# Power_Supply.net
KiCad netlist of a schematic drawn in Altium Designer
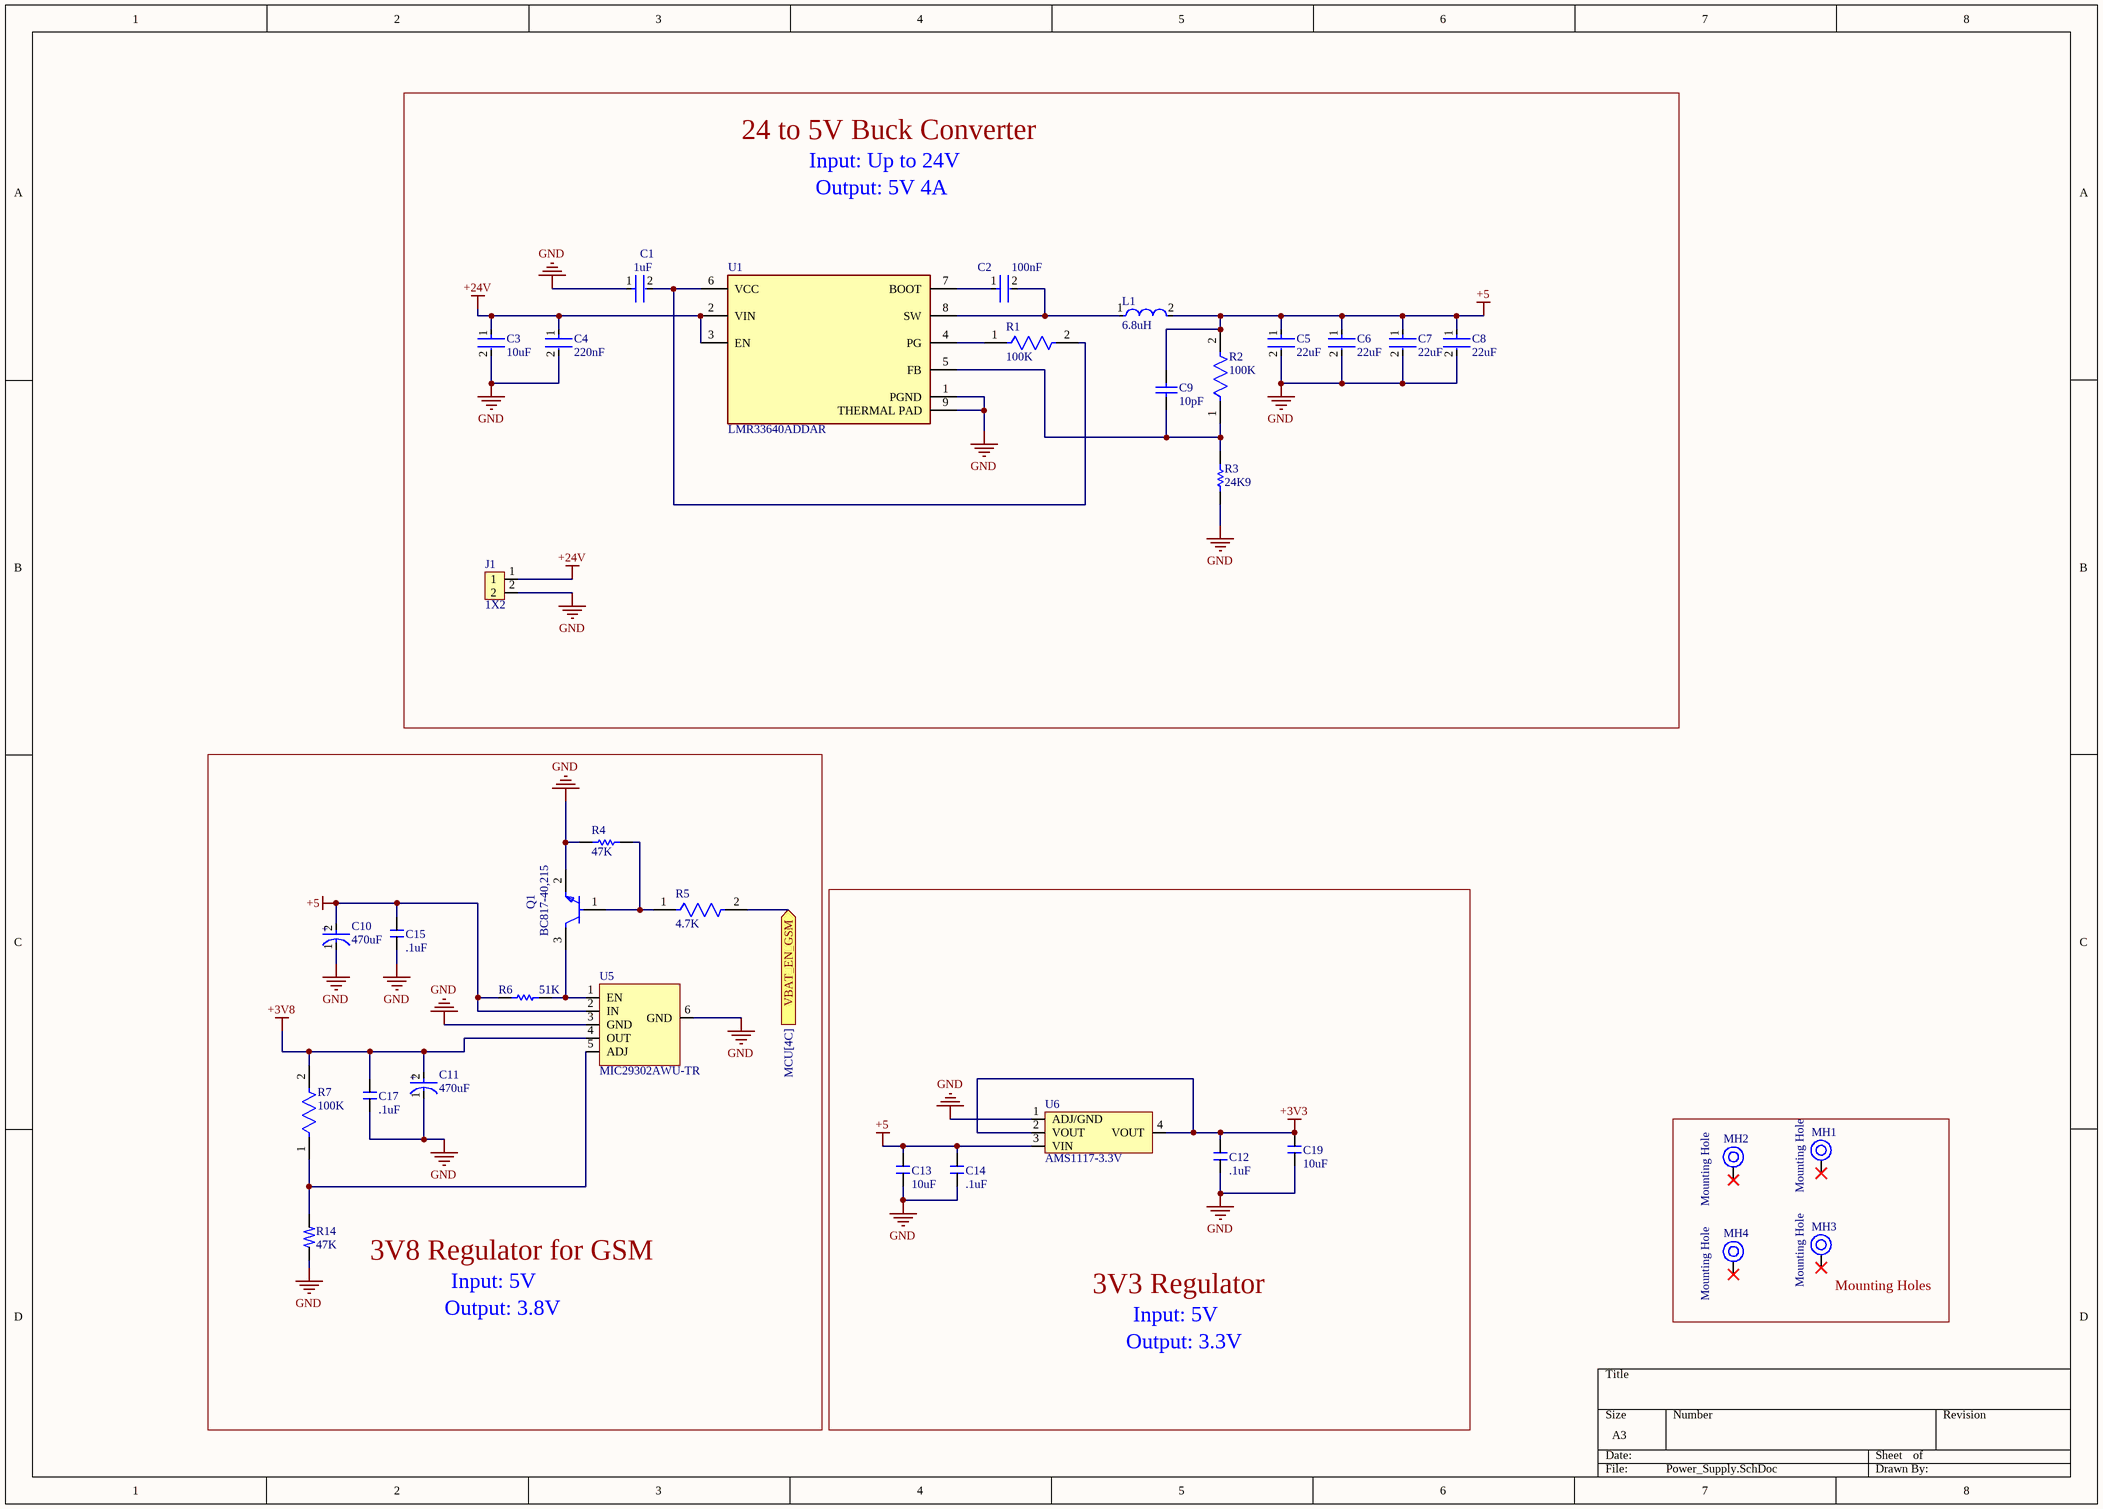
[diagram p0: Power_Supply.SchDoc]

(export (version "E")
  (design (tool "Eeschema 10.0.6"))
  (components
    (comp (ref "C1")
      (value "1uF")
      (footprint "FP-CL21-IPC_C")
      (description "CL21 Series 0805 1uF 50V ±10% Tolerance X7R Multilayer Ceramic Chip Capacitor")
      (fields (field (name "VOLTAGE") "50V") (field (name "TOLERANCE") "10%"))
      (libsource (lib "Altium Content Vault") (part "b4654b650e69147ec39a6b967a45e02"))
    )
    (comp (ref "C2")
      (value "100nF")
      (footprint "FP-CC0603-DA-MFG")
      (description "CAP CER 0.1UF 50V X7R 0603")
      (fields (field (name "MANUFACTURER") "YAGEO") (field (name "VOLTAGE") "50 V"))
      (libsource (lib "Altium Content Vault") (part "11868f565c42a9108669ba33697ecf6"))
    )
    (comp (ref "C3")
      (value "10uF")
      (footprint "FP-CL31-IPC_C")
      (description "CAP CER 10UF 50V X5R 1206")
      (fields (field (name "TOLERANCE") "10%") (field (name "MANUFACTURER") "Samsung"))
      (libsource (lib "Altium Content Vault") (part "11868f565c42a9108669ba33697ecf6"))
    )
    (comp (ref "C4")
      (value "220nF")
      (footprint "FP-C0805C-DN-MFG")
      (description "C0805 0.22 μF X7R 30ppm/°C 10.00% 50 V")
      (fields (field (name "MANUFACTURER") "KEMET"))
      (libsource (lib "Altium Content Vault") (part "b4654b650e69147ec39a6b967a45e02"))
    )
    (comp (ref "C5")
      (value "22uF")
      (footprint "FP-CL21-IPC_C")
      (description "CL21 Series 0805 22uF 16V ±20% Tolerance X5R Multilayer Ceramic Chip Capacitor")
      (fields (field (name "TOLERANCE") "20%"))
      (libsource (lib "Altium Content Vault") (part "b4654b650e69147ec39a6b967a45e02"))
    )
    (comp (ref "C6")
      (value "22uF")
      (footprint "FP-CL21-IPC_C")
      (description "CL21 Series 0805 22uF 16V ±20% Tolerance X5R Multilayer Ceramic Chip Capacitor")
      (fields (field (name "TOLERANCE") "20%"))
      (libsource (lib "Altium Content Vault") (part "b4654b650e69147ec39a6b967a45e02"))
    )
    (comp (ref "C7")
      (value "22uF")
      (footprint "FP-CL21-IPC_C")
      (description "CL21 Series 0805 22uF 16V ±20% Tolerance X5R Multilayer Ceramic Chip Capacitor")
      (fields (field (name "TOLERANCE") "20%"))
      (libsource (lib "Altium Content Vault") (part "b4654b650e69147ec39a6b967a45e02"))
    )
    (comp (ref "C8")
      (value "22uF")
      (footprint "FP-CL21-IPC_C")
      (description "CL21 Series 0805 22uF 16V ±20% Tolerance X5R Multilayer Ceramic Chip Capacitor")
      (fields (field (name "TOLERANCE") "20%"))
      (libsource (lib "Altium Content Vault") (part "b4654b650e69147ec39a6b967a45e02"))
    )
    (comp (ref "C9")
      (value "10pF")
      (footprint "CAPC1608X90X40ML10T20")
      (description "Chip Capacitor, 10 pF, +/- 5%, 50 V, -55 to 125 degC, 0603 (1608 Metric), RoHS, Tape and Reel")
      (fields (field (name "VOLTAGE") "50V") (field (name "TOLERANCE") "5%"))
      (libsource (lib "Altium Content Vault") (part "CAP-NP-2"))
    )
    (comp (ref "C10")
      (value "470uF")
      (footprint "FP-T491D477K006AT-MFG")
      (description "CAP TANT 470UF 10% 6.3V 2917")
      (fields (field (name "TOLERANCE") "10%"))
      (libsource (lib "Altium Content Vault") (part "a00bbbee19879c290e62620ae7e47b1"))
    )
    (comp (ref "C11")
      (value "470uF")
      (footprint "FP-T491D477K006AT-MFG")
      (description "CAP TANT 470UF 10% 6.3V 2917")
      (fields (field (name "TOLERANCE") "10%"))
      (libsource (lib "Altium Content Vault") (part "a00bbbee19879c290e62620ae7e47b1"))
    )
    (comp (ref "C12")
      (value ".1uF")
      (footprint "FB_0805")
      (description "Cap Ceramic 0.1uF 100V X7R 10% Pad SMD 0805 Fail Safe with Soft Termination 125C Automotive T/R")
      (fields
        (field (name "MANUFACTURER") "Murata")
        (field (name "MANUFACTURER PART NUMBER") "GCE21BR72A104KA01L")
      )
      (libsource (lib "Schlib1") (part "CAP .1 UF"))
    )
    (comp (ref "C13")
      (value "10uF")
      (footprint "Capacitor_0805")
      (description "16V 10uF X7R ±10% 0805 Multilayer Ceramic Capacitors MLCC - SMD/SMT ROHS")
      (fields
        (field (name "MANUFACTURER") "Samsung")
        (field (name "MANUFACTURER PART NUMBER") "CL21B106KOQNNNE")
      )
      (libsource (lib "Schlib1") (part "CAP 10uF 0805"))
    )
    (comp (ref "C14")
      (value ".1uF")
      (footprint "FB_0805")
      (description "Cap Ceramic 0.1uF 100V X7R 10% Pad SMD 0805 Fail Safe with Soft Termination 125C Automotive T/R")
      (fields
        (field (name "MANUFACTURER") "Murata")
        (field (name "MANUFACTURER PART NUMBER") "GCE21BR72A104KA01L")
      )
      (libsource (lib "Schlib1") (part "CAP .1 UF"))
    )
    (comp (ref "C15")
      (value ".1uF")
      (footprint "FB_0805")
      (description "Cap Ceramic 0.1uF 100V X7R 10% Pad SMD 0805 Fail Safe with Soft Termination 125C Automotive T/R")
      (fields
        (field (name "MANUFACTURER") "Murata")
        (field (name "MANUFACTURER PART NUMBER") "GCE21BR72A104KA01L")
      )
      (libsource (lib "Schlib1") (part "CAP .1 UF"))
    )
    (comp (ref "C17")
      (value ".1uF")
      (footprint "FB_0805")
      (description "Cap Ceramic 0.1uF 100V X7R 10% Pad SMD 0805 Fail Safe with Soft Termination 125C Automotive T/R")
      (fields
        (field (name "MANUFACTURER") "Murata")
        (field (name "MANUFACTURER PART NUMBER") "GCE21BR72A104KA01L")
      )
      (libsource (lib "Schlib1") (part "CAP .1 UF"))
    )
    (comp (ref "C19")
      (value "10uF")
      (footprint "Capacitor_0805")
      (description "16V 10uF X7R ±10% 0805 Multilayer Ceramic Capacitors MLCC - SMD/SMT ROHS")
      (fields
        (field (name "MANUFACTURER") "Samsung")
        (field (name "MANUFACTURER PART NUMBER") "CL21B106KOQNNNE")
      )
      (libsource (lib "Schlib1") (part "CAP 10uF 0805"))
    )
    (comp (ref "J1")
      (value "1X2")
      (footprint "Header 1x2 2.54mm")
      (description "Conn Unshrouded Header HDR 2 POS 2.54mm Solder ST Thru-Hole Automotive Carton")
      (fields
        (field (name "MANUFACTURER") "TE Connectivity")
        (field (name "MANUFACTURER PART NUMBER") "826629-2")
      )
      (libsource (lib "Schlib1") (part "Header 1X2 2.54 mm"))
    )
    (comp (ref "L1")
      (value "6.8uH")
      (footprint "FP-IHLP-2525CZ-FP_2_413x3-MFG")
      (description "Automotive Inductors, High Saturation Series 6.8uH 4.5A 60mΩ 20%")
      (fields (field (name "TOLERANCE") "20%"))
      (libsource (lib "Altium Content Vault") (part "725321dda6339637d4d059423bc1c3c"))
    )
    (comp (ref "MH1")
      (value "Mounting Hole")
      (footprint "MOUNTING")
      (fields (field (name "MANUFACTURER PART NUMBER") "NA"))
      (libsource (lib "Schlib1") (part "MH_3.5H_6D"))
    )
    (comp (ref "MH2")
      (value "Mounting Hole")
      (footprint "MOUNTING")
      (fields (field (name "MANUFACTURER PART NUMBER") "NA"))
      (libsource (lib "Schlib1") (part "MH_3.5H_6D"))
    )
    (comp (ref "MH3")
      (value "Mounting Hole")
      (footprint "MOUNTING")
      (fields (field (name "MANUFACTURER PART NUMBER") "NA"))
      (libsource (lib "Schlib1") (part "MH_3.5H_6D"))
    )
    (comp (ref "MH4")
      (value "Mounting Hole")
      (footprint "MOUNTING")
      (fields (field (name "MANUFACTURER PART NUMBER") "NA"))
      (libsource (lib "Schlib1") (part "MH_3.5H_6D"))
    )
    (comp (ref "Q1")
      (value "BC817-40,215")
      (footprint "FP-SOT23-MFG")
      (description "TRANS NPN 45V 0.5A SOT23")
      (fields
        (field (name "OCTOPART") "https://octopart.com/bc817-40%2C215-nexperia-78739081")
        (field (name "MANUFACTURER") "Nexperia")
      )
      (libsource (lib "Altium Content Vault") (part "b44e953556f554d0102664c7d152cb4"))
    )
    (comp (ref "R1")
      (value "100K")
      (footprint "FP-RT0805-MFG")
      (description "RES SMD 100K OHM 0.1% 1/8W 0805")
      (fields
        (field (name "MANUFACTURER PART NUMBER") "RT0805BRD07100KL")
        (field (name "TOLERANCE") "0.0025")
      )
      (libsource (lib "Altium Content Vault") (part "1029c3af85768c4190bb7ad29bc67b5"))
    )
    (comp (ref "R2")
      (value "100K")
      (footprint "FP-RT0805-MFG")
      (description "RES SMD 100K OHM 0.1% 1/8W 0805")
      (fields
        (field (name "MANUFACTURER PART NUMBER") "RT0805BRD07100KL")
        (field (name "TOLERANCE") "0.0025")
      )
      (libsource (lib "Altium Content Vault") (part "1029c3af85768c4190bb7ad29bc67b5"))
    )
    (comp (ref "R3")
      (value "24K9")
      (footprint "RESC0805(2012)_L")
      (description "24K9 0.125W 1% 0805 (2012 Metric)  SMD")
      (fields (field (name "POWER") "0.125 W") (field (name "TOLERANCE") "1 %"))
      (libsource (lib "Altium Content Vault") (part "RES"))
    )
    (comp (ref "R4")
      (value "47K")
      (footprint "RESC2013X60X35NL10T20")
      (description "Chip Resistor, 47 KOhm, +/- 1%, 0.125 W, -55 to 155 degC, 0805 (2012 Metric), RoHS, Tape and Reel")
      (fields (field (name "MANUFACTURER") "Yageo"))
      (libsource (lib "Altium Content Vault") (part "RES-2"))
    )
    (comp (ref "R5")
      (value "4.7K")
      (footprint "FP-CRCW0805-e3-IPC_B")
      (description "RES Thick Film, 4.7kΩ, 1%, 0.125W, 100ppm/°C, 0805")
      (fields (field (name "TOLERANCE") "1%"))
      (libsource (lib "Altium Content Vault") (part "1029c3af85768c4190bb7ad29bc67b5"))
    )
    (comp (ref "R6")
      (value "51K")
      (footprint "RESC2013X50X30NL20T20")
      (fields (field (name "MANUFACTURER") "Vishay Dale") (field (name "PART NUMBER") "CRCW080551K0FKEA"))
      (libsource (lib "Altium Content Vault") (part "RES"))
    )
    (comp (ref "R7")
      (value "100K")
      (footprint "FP-RT0805-MFG")
      (description "RES SMD 100K OHM 0.1% 1/8W 0805")
      (fields
        (field (name "MANUFACTURER PART NUMBER") "RT0805BRD07100KL")
        (field (name "TOLERANCE") "0.0025")
      )
      (libsource (lib "Altium Content Vault") (part "1029c3af85768c4190bb7ad29bc67b5"))
    )
    (comp (ref "R14")
      (value "47K")
      (footprint "Resistor_0805")
      (description "125Mw Thick Film Resistors 100Ppm/ 1% 47K 0805 Chip Resistor Surface Mount Rohs")
      (fields
        (field (name "MANUFACTURER") "Yageo")
        (field (name "MANUFACTURER PART NUMBER") "RC0805FR-0747KL")
      )
      (libsource (lib "Schlib1") (part "RES 47K 0805"))
    )
    (comp (ref "U1")
      (value "LMR33640ADDAR")
      (footprint "FP-DDA0008J-IPC_A")
      (description "36V 4A 400KHZ REGULATOR")
      (libsource (lib "Altium Content Vault") (part "88f7987fbe75384f65cab7a50dd0ee1"))
    )
    (comp (ref "U5")
      (value "MIC29302AWU-TR")
      (footprint "TO-263-5")
      (description "IC REG LDO ADJ 3A TO263-5")
      (fields (field (name "MANUFACTURER") "Microchip"))
      (libsource (lib "Schlib1") (part "LDO MIC29302AWU-TR"))
    )
    (comp (ref "U6")
      (value "AMS1117-3.3V")
      (footprint "SOT-223")
      (description "1A Fixed 3.3V 18V SOT-223 Voltage Regulators - Linear, Low Drop Out (LDO) Regulators ROHS")
      (fields (field (name "MANUFACTURER") "Tech Public"))
      (libsource (lib "Schlib1") (part "AMS1117-3.3V"))
    )
  )
  (nets
    (net (code "1") (name "+3V3") (class "Default")
      (node (ref "C12") (pin "1") (pinfunction "1_1") (pintype "passive"))
      (node (ref "C19") (pin "1") (pinfunction "1_1") (pintype "passive"))
      (node (ref "U6") (pin "2") (pinfunction "VOUT_2") (pintype "passive"))
      (node (ref "U6") (pin "4") (pinfunction "VOUT_4") (pintype "passive"))
    )
    (net (code "2") (name "+3V8") (class "Default")
      (node (ref "C11") (pin "2") (pinfunction "A_2") (pintype "passive"))
      (node (ref "C17") (pin "1") (pinfunction "1_1") (pintype "passive"))
      (node (ref "R7") (pin "2") (pinfunction "2_2") (pintype "passive"))
      (node (ref "U5") (pin "4") (pinfunction "OUT_4") (pintype "passive"))
    )
    (net (code "3") (name "+5") (class "Default")
      (node (ref "C10") (pin "2") (pinfunction "A_2") (pintype "passive"))
      (node (ref "C13") (pin "1") (pinfunction "1_1") (pintype "passive"))
      (node (ref "C14") (pin "1") (pinfunction "1_1") (pintype "passive"))
      (node (ref "C15") (pin "1") (pinfunction "1_1") (pintype "passive"))
      (node (ref "C5") (pin "1") (pinfunction "1_1") (pintype "passive"))
      (node (ref "C6") (pin "1") (pinfunction "1_1") (pintype "passive"))
      (node (ref "C7") (pin "1") (pinfunction "1_1") (pintype "passive"))
      (node (ref "C8") (pin "1") (pinfunction "1_1") (pintype "passive"))
      (node (ref "C9") (pin "2") (pinfunction "2_2") (pintype "passive"))
      (node (ref "L1") (pin "2") (pinfunction "2_2") (pintype "passive"))
      (node (ref "R2") (pin "2") (pinfunction "2_2") (pintype "passive"))
      (node (ref "R6") (pin "2") (pinfunction "2_2") (pintype "passive"))
      (node (ref "U5") (pin "2") (pinfunction "IN_2") (pintype "passive"))
      (node (ref "U6") (pin "3") (pinfunction "VIN_3") (pintype "passive"))
    )
    (net (code "4") (name "+24V") (class "Default")
      (node (ref "C3") (pin "1") (pinfunction "1_1") (pintype "passive"))
      (node (ref "C4") (pin "1") (pinfunction "1_1") (pintype "passive"))
      (node (ref "J1") (pin "1") (pinfunction "1_1") (pintype "passive"))
      (node (ref "U1") (pin "2") (pinfunction "VIN_2") (pintype "power_in"))
      (node (ref "U1") (pin "3") (pinfunction "EN_3") (pintype "passive"))
    )
    (net (code "5") (name "/VBAT_EN_GSM") (class "Default")
      (node (ref "R5") (pin "2") (pinfunction "2_2") (pintype "passive"))
    )
    (net (code "6") (name "GND") (class "Default")
      (node (ref "C1") (pin "1") (pinfunction "1_1") (pintype "passive"))
      (node (ref "C10") (pin "1") (pinfunction "C_1") (pintype "passive"))
      (node (ref "C11") (pin "1") (pinfunction "C_1") (pintype "passive"))
      (node (ref "C12") (pin "2") (pinfunction "2_2") (pintype "passive"))
      (node (ref "C13") (pin "2") (pinfunction "2_2") (pintype "passive"))
      (node (ref "C14") (pin "2") (pinfunction "2_2") (pintype "passive"))
      (node (ref "C15") (pin "2") (pinfunction "2_2") (pintype "passive"))
      (node (ref "C17") (pin "2") (pinfunction "2_2") (pintype "passive"))
      (node (ref "C19") (pin "2") (pinfunction "2_2") (pintype "passive"))
      (node (ref "C3") (pin "2") (pinfunction "2_2") (pintype "passive"))
      (node (ref "C4") (pin "2") (pinfunction "2_2") (pintype "passive"))
      (node (ref "C5") (pin "2") (pinfunction "2_2") (pintype "passive"))
      (node (ref "C6") (pin "2") (pinfunction "2_2") (pintype "passive"))
      (node (ref "C7") (pin "2") (pinfunction "2_2") (pintype "passive"))
      (node (ref "C8") (pin "2") (pinfunction "2_2") (pintype "passive"))
      (node (ref "J1") (pin "2") (pinfunction "2_2") (pintype "passive"))
      (node (ref "Q1") (pin "2") (pinfunction "E_2") (pintype "passive"))
      (node (ref "R14") (pin "1") (pinfunction "1_1") (pintype "passive"))
      (node (ref "R3") (pin "1") (pinfunction "1_1") (pintype "passive"))
      (node (ref "R4") (pin "1") (pinfunction "1_1") (pintype "passive"))
      (node (ref "U1") (pin "1") (pinfunction "PGND_1") (pintype "power_in"))
      (node (ref "U1") (pin "9") (pinfunction "THERMAL_PAD_9") (pintype "power_in"))
      (node (ref "U5") (pin "3") (pinfunction "GND_3") (pintype "passive"))
      (node (ref "U5") (pin "6") (pinfunction "GND_6") (pintype "passive"))
      (node (ref "U6") (pin "1") (pinfunction "ADJ/GND_1") (pintype "passive"))
    )
    (net (code "7") (name "Net-(Q1-B)") (class "Default")
      (node (ref "Q1") (pin "1") (pinfunction "B_1") (pintype "passive"))
      (node (ref "R4") (pin "2") (pinfunction "2_2") (pintype "passive"))
      (node (ref "R5") (pin "1") (pinfunction "1_1") (pintype "passive"))
    )
    (net (code "8") (name "Net-(Q1-C)") (class "Default")
      (node (ref "Q1") (pin "3") (pinfunction "C_3") (pintype "passive"))
      (node (ref "R6") (pin "1") (pinfunction "1_1") (pintype "passive"))
      (node (ref "U5") (pin "1") (pinfunction "EN_1") (pintype "passive"))
    )
    (net (code "9") (name "Net-(U1-BOOT)") (class "Default")
      (node (ref "C2") (pin "1") (pinfunction "1_1") (pintype "passive"))
      (node (ref "U1") (pin "7") (pinfunction "BOOT_7") (pintype "power_in"))
    )
    (net (code "10") (name "Net-(U1-FB)") (class "Default")
      (node (ref "C9") (pin "1") (pinfunction "1_1") (pintype "passive"))
      (node (ref "R2") (pin "1") (pinfunction "1_1") (pintype "passive"))
      (node (ref "R3") (pin "2") (pinfunction "2_2") (pintype "passive"))
      (node (ref "U1") (pin "5") (pinfunction "FB_5") (pintype "passive"))
    )
    (net (code "11") (name "Net-(U1-PG)") (class "Default")
      (node (ref "R1") (pin "1") (pinfunction "1_1") (pintype "passive"))
      (node (ref "U1") (pin "4") (pinfunction "PG_4") (pintype "passive"))
    )
    (net (code "12") (name "Net-(U1-SW)") (class "Default")
      (node (ref "C2") (pin "2") (pinfunction "2_2") (pintype "passive"))
      (node (ref "L1") (pin "1") (pinfunction "1_1") (pintype "passive"))
      (node (ref "U1") (pin "8") (pinfunction "SW_8") (pintype "power_in"))
    )
    (net (code "13") (name "Net-(U1-VCC)") (class "Default")
      (node (ref "C1") (pin "2") (pinfunction "2_2") (pintype "passive"))
      (node (ref "R1") (pin "2") (pinfunction "2_2") (pintype "passive"))
      (node (ref "U1") (pin "6") (pinfunction "VCC_6") (pintype "power_in"))
    )
    (net (code "14") (name "Net-(U5-ADJ)") (class "Default")
      (node (ref "R14") (pin "2") (pinfunction "2_2") (pintype "passive"))
      (node (ref "R7") (pin "1") (pinfunction "1_1") (pintype "passive"))
      (node (ref "U5") (pin "5") (pinfunction "ADJ_5") (pintype "passive"))
    )
    (net (code "15") (name "unconnected-(MH1-Pad1)") (class "Default")
      (node (ref "MH1") (pin "1") (pinfunction "1_1") (pintype "passive+no_connect"))
    )
    (net (code "16") (name "unconnected-(MH2-Pad1)") (class "Default")
      (node (ref "MH2") (pin "1") (pinfunction "1_1") (pintype "passive+no_connect"))
    )
    (net (code "17") (name "unconnected-(MH3-Pad1)") (class "Default")
      (node (ref "MH3") (pin "1") (pinfunction "1_1") (pintype "passive+no_connect"))
    )
    (net (code "18") (name "unconnected-(MH4-Pad1)") (class "Default")
      (node (ref "MH4") (pin "1") (pinfunction "1_1") (pintype "passive+no_connect"))
    )
  )
)
